# misc.net
KiCad netlist of a schematic drawn in Altium Designer
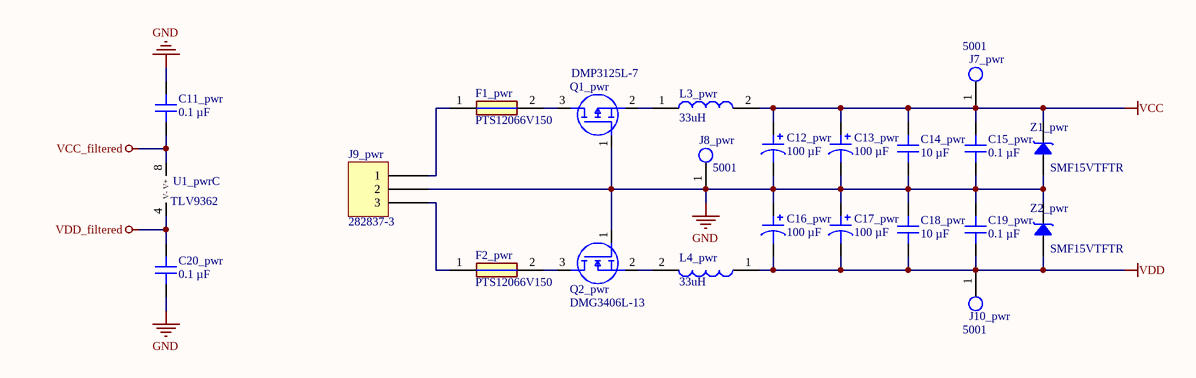
[diagram p0: misc.SchDoc]

(export (version "E")
  (design (tool "Eeschema 10.0.6"))
  (components
    (comp (ref "C11_pwr")
      (value "0.1 µF")
      (footprint "CAP 1206_3216 - 0.8MM")
      (description "CAP CER 0.1UF 50V X7R 1206")
      (fields
        (field (name "PART NUMBER") "885012208087")
        (field (name "CAPACITANCE") "0.1 µF")
        (field (name "MANUFACTURER") "Würth Elektronik")
      )
      (libsource (lib "Celestial Altium Library - altium_library") (part "Capacitor"))
    )
    (comp (ref "C12_pwr")
      (value "100 µF")
      (footprint "CAP ALSMD 8.3MM H10.5MM")
      (description "CAP ALUM 100UF 20% 50V SMD")
      (fields (field (name "PART NUMBER") "50TZV100M8X10.5") (field (name "MANUFACTURER") "Rubycon"))
      (libsource (lib "Celestial Altium Library - altium_library") (part "Polarised Capacitor"))
    )
    (comp (ref "C13_pwr")
      (value "100 µF")
      (footprint "CAP ALSMD 8.3MM H10.5MM")
      (description "CAP ALUM 100UF 20% 50V SMD")
      (fields (field (name "PART NUMBER") "50TZV100M8X10.5") (field (name "MANUFACTURER") "Rubycon"))
      (libsource (lib "Celestial Altium Library - altium_library") (part "Polarised Capacitor"))
    )
    (comp (ref "C14_pwr")
      (value "10 µF")
      (footprint "CAP 1206_3216 - 0.8MM")
      (description "CAP CER 10UF 25V X7R 1206")
      (fields
        (field (name "PART NUMBER") "885012208069")
        (field (name "CAPACITANCE") "10 µF")
        (field (name "MANUFACTURER") "Würth Elektronik")
      )
      (libsource (lib "Celestial Altium Library - altium_library") (part "Capacitor"))
    )
    (comp (ref "C15_pwr")
      (value "0.1 µF")
      (footprint "CAP 1206_3216 - 0.8MM")
      (description "CAP CER 0.1UF 50V X7R 1206")
      (fields
        (field (name "PART NUMBER") "885012208087")
        (field (name "CAPACITANCE") "0.1 µF")
        (field (name "MANUFACTURER") "Würth Elektronik")
      )
      (libsource (lib "Celestial Altium Library - altium_library") (part "Capacitor"))
    )
    (comp (ref "C16_pwr")
      (value "100 µF")
      (footprint "CAP ALSMD 8.3MM H10.5MM")
      (description "CAP ALUM 100UF 20% 50V SMD")
      (fields (field (name "PART NUMBER") "50TZV100M8X10.5") (field (name "MANUFACTURER") "Rubycon"))
      (libsource (lib "Celestial Altium Library - altium_library") (part "Polarised Capacitor"))
    )
    (comp (ref "C17_pwr")
      (value "100 µF")
      (footprint "CAP ALSMD 8.3MM H10.5MM")
      (description "CAP ALUM 100UF 20% 50V SMD")
      (fields (field (name "PART NUMBER") "50TZV100M8X10.5") (field (name "MANUFACTURER") "Rubycon"))
      (libsource (lib "Celestial Altium Library - altium_library") (part "Polarised Capacitor"))
    )
    (comp (ref "C18_pwr")
      (value "10 µF")
      (footprint "CAP 1206_3216 - 0.8MM")
      (description "CAP CER 10UF 25V X7R 1206")
      (fields
        (field (name "PART NUMBER") "885012208069")
        (field (name "CAPACITANCE") "10 µF")
        (field (name "MANUFACTURER") "Würth Elektronik")
      )
      (libsource (lib "Celestial Altium Library - altium_library") (part "Capacitor"))
    )
    (comp (ref "C19_pwr")
      (value "0.1 µF")
      (footprint "CAP 1206_3216 - 0.8MM")
      (description "CAP CER 0.1UF 50V X7R 1206")
      (fields
        (field (name "PART NUMBER") "885012208087")
        (field (name "CAPACITANCE") "0.1 µF")
        (field (name "MANUFACTURER") "Würth Elektronik")
      )
      (libsource (lib "Celestial Altium Library - altium_library") (part "Capacitor"))
    )
    (comp (ref "C20_pwr")
      (value "0.1 µF")
      (footprint "CAP 1206_3216 - 0.8MM")
      (description "CAP CER 0.1UF 50V X7R 1206")
      (fields
        (field (name "PART NUMBER") "885012208087")
        (field (name "CAPACITANCE") "0.1 µF")
        (field (name "MANUFACTURER") "Würth Elektronik")
      )
      (libsource (lib "Celestial Altium Library - altium_library") (part "Capacitor"))
    )
    (comp (ref "F1_pwr")
      (value "PTS12066V150")
      (footprint "FUSC3216X90N")
      (description "Fuse")
      (fields
        (field (name "MOUSER PART NUMBER") "504-PTS12066V150")
        (field (name "ARROW PART NUMBER") "PTS120660V005")
      )
      (libsource (lib "za_koncar") (part "PTS12066V150"))
    )
    (comp (ref "F2_pwr")
      (value "PTS12066V150")
      (footprint "FUSC3216X90N")
      (description "Fuse")
      (fields
        (field (name "MOUSER PART NUMBER") "504-PTS12066V150")
        (field (name "ARROW PART NUMBER") "PTS120660V005")
      )
      (libsource (lib "za_koncar") (part "PTS12066V150"))
    )
    (comp (ref "J7_pwr")
      (value "5001")
      (footprint "FP-5001-MFG")
      (description "PC TEST POINT MINIATURE BLACK")
      (libsource (lib "za_koncar") (part "CMP-2000-05181-2"))
    )
    (comp (ref "J8_pwr")
      (value "5001")
      (footprint "FP-5001-MFG")
      (description "PC TEST POINT MINIATURE BLACK")
      (libsource (lib "za_koncar") (part "CMP-2000-05181-2"))
    )
    (comp (ref "J9_pwr")
      (value "282837-3")
      (footprint "TE 282837-3")
      (description "TERM BLK 3P SIDE ENT 5.08MM PCB")
      (fields (field (name "MANUFACTURER") "TE Connectivity AMP Connectors") (field (name "VOLTAGE") "300 V"))
      (libsource (lib "Celestial Altium Library - altium_library") (part "3 Pin"))
    )
    (comp (ref "J10_pwr")
      (value "5001")
      (footprint "FP-5001-MFG")
      (description "PC TEST POINT MINIATURE BLACK")
      (libsource (lib "za_koncar") (part "CMP-2000-05181-2"))
    )
    (comp (ref "L3_pwr")
      (value "33uH")
      (footprint "SamacSys:INDPM116102X400N")
      (description "Inductor")
      (fields
        (field (name "MANUFACTURER_PART_NUMBER") "AMRM00101040330MA1")
        (field (name "MOUSER PART NUMBER") "673-AMRM101040330MA1")
      )
      (libsource (lib "za_koncar") (part "AMRM00101040330MA1"))
    )
    (comp (ref "L4_pwr")
      (value "33uH")
      (footprint "SamacSys:INDPM116102X400N")
      (description "Inductor")
      (fields
        (field (name "MANUFACTURER_PART_NUMBER") "AMRM00101040330MA1")
        (field (name "MOUSER PART NUMBER") "673-AMRM101040330MA1")
      )
      (libsource (lib "za_koncar") (part "AMRM00101040330MA1"))
    )
    (comp (ref "Q1_pwr")
      (value "DMP3125L-7")
      (footprint "SamacSys:SOT96P240X110-3N")
      (description "MOSFET (P-Channel)")
      (fields (field (name "MOUSER PART NUMBER") "621-DMP3125L-7"))
      (libsource (lib "*") (part "DMP3125L-7"))
    )
    (comp (ref "Q2_pwr")
      (value "DMG3406L-13")
      (footprint "SOT96P240X110-3N")
      (description "MOSFET (N-Channel)")
      (fields (field (name "MOUSER PART NUMBER") "621-DMG3406L-13"))
      (libsource (lib "za_koncar") (part "DMG3406L-13"))
    )
    (comp (ref "U1_pwr")
      (value "TLV9362")
      (footprint "za_koncar:SOIC8-127P600X175-8N")
      (description "TLV936x 10-MHz, 40-V, RRO, Operational Amplifie")
      (libsource (lib "za_koncar") (part "TLV9362"))
    )
    (comp (ref "Z1_pwr")
      (value "SMF15VTFTR")
      (footprint "SMF15VTFTR")
      (description "Zener Diode")
      (fields (field (name "MOUSER PART NUMBER") "755-SMF15VTFTR"))
      (libsource (lib "za_koncar") (part "SMF15VTFTR"))
    )
    (comp (ref "Z2_pwr")
      (value "SMF15VTFTR")
      (footprint "SMF15VTFTR")
      (description "Zener Diode")
      (fields (field (name "MOUSER PART NUMBER") "755-SMF15VTFTR"))
      (libsource (lib "za_koncar") (part "SMF15VTFTR"))
    )
  )
  (nets
    (net (code "1") (name "GND") (class "Default")
      (node (ref "C11_pwr") (pin "2") (pinfunction "2_2") (pintype "passive"))
      (node (ref "C12_pwr") (pin "2") (pinfunction "2_2") (pintype "passive"))
      (node (ref "C13_pwr") (pin "2") (pinfunction "2_2") (pintype "passive"))
      (node (ref "C14_pwr") (pin "1") (pinfunction "1_1") (pintype "passive"))
      (node (ref "C15_pwr") (pin "1") (pinfunction "1_1") (pintype "passive"))
      (node (ref "C16_pwr") (pin "1") (pinfunction "1_1") (pintype "passive"))
      (node (ref "C17_pwr") (pin "1") (pinfunction "1_1") (pintype "passive"))
      (node (ref "C18_pwr") (pin "2") (pinfunction "2_2") (pintype "passive"))
      (node (ref "C19_pwr") (pin "2") (pinfunction "2_2") (pintype "passive"))
      (node (ref "C20_pwr") (pin "1") (pinfunction "1_1") (pintype "passive"))
      (node (ref "J8_pwr") (pin "1") (pinfunction "1_1") (pintype "passive"))
      (node (ref "J9_pwr") (pin "2") (pinfunction "2_2") (pintype "passive"))
      (node (ref "Q1_pwr") (pin "1") (pinfunction "G_1") (pintype "passive"))
      (node (ref "Q2_pwr") (pin "1") (pinfunction "G_1") (pintype "passive"))
      (node (ref "Z1_pwr") (pin "2") (pinfunction "2_2") (pintype "passive"))
      (node (ref "Z2_pwr") (pin "1") (pinfunction "1_1") (pintype "passive"))
    )
    (net (code "2") (name "Net-(F1_pwr-Pad1)") (class "Default")
      (node (ref "F1_pwr") (pin "1") (pinfunction "1_1") (pintype "passive"))
      (node (ref "J9_pwr") (pin "1") (pinfunction "1_1") (pintype "passive"))
    )
    (net (code "3") (name "Net-(F2_pwr-Pad1)") (class "Default")
      (node (ref "F2_pwr") (pin "1") (pinfunction "1_1") (pintype "passive"))
      (node (ref "J9_pwr") (pin "3") (pinfunction "3_3") (pintype "passive"))
    )
    (net (code "4") (name "Net-(Q1_pwr-D)") (class "Default")
      (node (ref "F1_pwr") (pin "2") (pinfunction "2_2") (pintype "passive"))
      (node (ref "Q1_pwr") (pin "3") (pinfunction "D_3") (pintype "passive"))
    )
    (net (code "5") (name "Net-(Q1_pwr-S)") (class "Default")
      (node (ref "L3_pwr") (pin "1") (pinfunction "1_1") (pintype "passive"))
      (node (ref "Q1_pwr") (pin "2") (pinfunction "S_2") (pintype "passive"))
    )
    (net (code "6") (name "Net-(Q2_pwr-D)") (class "Default")
      (node (ref "F2_pwr") (pin "2") (pinfunction "2_2") (pintype "passive"))
      (node (ref "Q2_pwr") (pin "3") (pinfunction "D_3") (pintype "passive"))
    )
    (net (code "7") (name "Net-(Q2_pwr-S)") (class "Default")
      (node (ref "L4_pwr") (pin "2") (pinfunction "2_2") (pintype "passive"))
      (node (ref "Q2_pwr") (pin "2") (pinfunction "S_2") (pintype "passive"))
    )
    (net (code "8") (name "VCC") (class "Default")
      (node (ref "C12_pwr") (pin "1") (pinfunction "1_1") (pintype "passive"))
      (node (ref "C13_pwr") (pin "1") (pinfunction "1_1") (pintype "passive"))
      (node (ref "C14_pwr") (pin "2") (pinfunction "2_2") (pintype "passive"))
      (node (ref "C15_pwr") (pin "2") (pinfunction "2_2") (pintype "passive"))
      (node (ref "J7_pwr") (pin "1") (pinfunction "1_1") (pintype "passive"))
      (node (ref "L3_pwr") (pin "2") (pinfunction "2_2") (pintype "passive"))
      (node (ref "Z1_pwr") (pin "1") (pinfunction "1_1") (pintype "passive"))
    )
    (net (code "9") (name "VCC_filtered") (class "Default")
      (node (ref "C11_pwr") (pin "1") (pinfunction "1_1") (pintype "passive"))
      (node (ref "U1_pwr") (pin "8") (pinfunction "V+_8") (pintype "power_in"))
    )
    (net (code "10") (name "VDD") (class "Default")
      (node (ref "C16_pwr") (pin "2") (pinfunction "2_2") (pintype "passive"))
      (node (ref "C17_pwr") (pin "2") (pinfunction "2_2") (pintype "passive"))
      (node (ref "C18_pwr") (pin "1") (pinfunction "1_1") (pintype "passive"))
      (node (ref "C19_pwr") (pin "1") (pinfunction "1_1") (pintype "passive"))
      (node (ref "J10_pwr") (pin "1") (pinfunction "1_1") (pintype "passive"))
      (node (ref "L4_pwr") (pin "1") (pinfunction "1_1") (pintype "passive"))
      (node (ref "Z2_pwr") (pin "2") (pinfunction "2_2") (pintype "passive"))
    )
    (net (code "11") (name "VDD_filtered") (class "Default")
      (node (ref "C20_pwr") (pin "2") (pinfunction "2_2") (pintype "passive"))
      (node (ref "U1_pwr") (pin "4") (pinfunction "V-_4") (pintype "power_in"))
    )
  )
)
